# probings.net
KiCad netlist of a schematic drawn in EAGLE
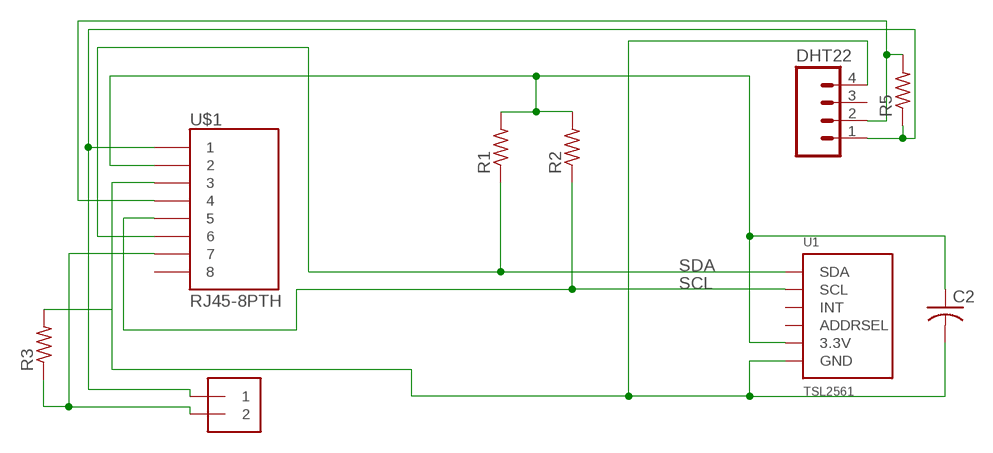
[diagram p0: schematic, sheet 1]

(export (version "E")
  (design (tool "Eeschema 10.0.6"))
  (components
    (comp (ref "C2")
      (value "C-US025-024X044")
      (footprint "eagle-import:C025-024X044")
      (libsource (lib "eagle-import") (part "C-US025-024X044"))
    )
    (comp (ref "DHT22")
      (value "M04PTH")
      (footprint "eagle-import:1X04")
      (libsource (lib "eagle-import") (part "M04PTH"))
    )
    (comp (ref "J1")
      (value "1X2-3.5MM")
      (footprint "eagle-import:1X2-3.5MM")
      (libsource (lib "eagle-import") (part "1X2-3.5MM"))
    )
    (comp (ref "R1")
      (value "R-US_0204/7")
      (footprint "eagle-import:0204_7")
      (libsource (lib "eagle-import") (part "R-US_0204/7"))
    )
    (comp (ref "R2")
      (value "R-US_0204/7")
      (footprint "eagle-import:0204_7")
      (libsource (lib "eagle-import") (part "R-US_0204/7"))
    )
    (comp (ref "R3")
      (value "R-US_0204/7")
      (footprint "eagle-import:0204_7")
      (libsource (lib "eagle-import") (part "R-US_0204/7"))
    )
    (comp (ref "R5")
      (value "R-US_0204/7")
      (footprint "eagle-import:0204_7")
      (libsource (lib "eagle-import") (part "R-US_0204/7"))
    )
    (comp (ref "U$1")
      (value "RJ45-8PTH")
      (footprint "eagle-import:RJ45-8")
      (libsource (lib "eagle-import") (part "RJ45-8PTH"))
    )
    (comp (ref "U1")
      (value "TSL2561")
      (footprint "eagle-import:TSL2561_FN")
      (libsource (lib "eagle-import") (part "TSL2561"))
    )
  )
  (nets
    (net (code "1") (name "/SCL") (class "Default")
      (node (ref "R2") (pin "1") (pinfunction "1_1") (pintype "passive"))
      (node (ref "U$1") (pin "5") (pinfunction "5_5") (pintype "bidirectional"))
      (node (ref "U1") (pin "CLK") (pinfunction "SCL_CLK") (pintype "bidirectional"))
    )
    (net (code "2") (name "/SDA") (class "Default")
      (node (ref "R1") (pin "1") (pinfunction "1_1") (pintype "passive"))
      (node (ref "U$1") (pin "6") (pinfunction "6_6") (pintype "bidirectional"))
      (node (ref "U1") (pin "DATA") (pinfunction "SDA_DATA") (pintype "bidirectional"))
    )
    (net (code "3") (name "Net-(DHT22-Pad1)") (class "Default")
      (node (ref "DHT22") (pin "1") (pinfunction "1_1") (pintype "passive"))
      (node (ref "J1") (pin "1") (pinfunction "1_1") (pintype "passive"))
      (node (ref "R5") (pin "1") (pinfunction "1_1") (pintype "passive"))
      (node (ref "U$1") (pin "1") (pinfunction "1_1") (pintype "bidirectional"))
    )
    (net (code "4") (name "Net-(DHT22-Pad2)") (class "Default")
      (node (ref "DHT22") (pin "2") (pinfunction "2_2") (pintype "passive"))
      (node (ref "R5") (pin "2") (pinfunction "2_2") (pintype "passive"))
      (node (ref "U$1") (pin "4") (pinfunction "4_4") (pintype "bidirectional"))
    )
    (net (code "5") (name "Net-(J1-Pad2)") (class "Default")
      (node (ref "J1") (pin "2") (pinfunction "2_2") (pintype "passive"))
      (node (ref "R3") (pin "1") (pinfunction "1_1") (pintype "passive"))
      (node (ref "U$1") (pin "7") (pinfunction "7_7") (pintype "bidirectional"))
    )
    (net (code "6") (name "Net-(U1-3.3V)") (class "Default")
      (node (ref "C2") (pin "1") (pinfunction "1_1") (pintype "passive"))
      (node (ref "R1") (pin "2") (pinfunction "2_2") (pintype "passive"))
      (node (ref "R2") (pin "2") (pinfunction "2_2") (pintype "passive"))
      (node (ref "U$1") (pin "2") (pinfunction "2_2") (pintype "bidirectional"))
      (node (ref "U1") (pin "VDD") (pinfunction "3.3V_VDD") (pintype "bidirectional"))
    )
    (net (code "7") (name "Net-(U1-GND)") (class "Default")
      (node (ref "C2") (pin "2") (pinfunction "2_2") (pintype "passive"))
      (node (ref "DHT22") (pin "4") (pinfunction "4_4") (pintype "passive"))
      (node (ref "R3") (pin "2") (pinfunction "2_2") (pintype "passive"))
      (node (ref "U$1") (pin "3") (pinfunction "3_3") (pintype "bidirectional"))
      (node (ref "U1") (pin "VSS") (pinfunction "GND_VSS") (pintype "bidirectional"))
    )
    (net (code "8") (name "unconnected-(DHT22-Pad3)") (class "Default")
      (node (ref "DHT22") (pin "3") (pinfunction "3_3") (pintype "passive"))
    )
    (net (code "9") (name "unconnected-(U$1-Pad8)") (class "Default")
      (node (ref "U$1") (pin "8") (pinfunction "8_8") (pintype "bidirectional"))
    )
    (net (code "10") (name "unconnected-(U1-ADDRSEL-PadADR)") (class "Default")
      (node (ref "U1") (pin "ADR") (pinfunction "ADDRSEL_ADR") (pintype "bidirectional"))
    )
    (net (code "11") (name "unconnected-(U1-PadINT)") (class "Default")
      (node (ref "U1") (pin "INT") (pinfunction "INT_INT") (pintype "bidirectional"))
    )
  )
)
